# DS1339_RTC_Module.net
KiCad netlist of a schematic drawn in EAGLE
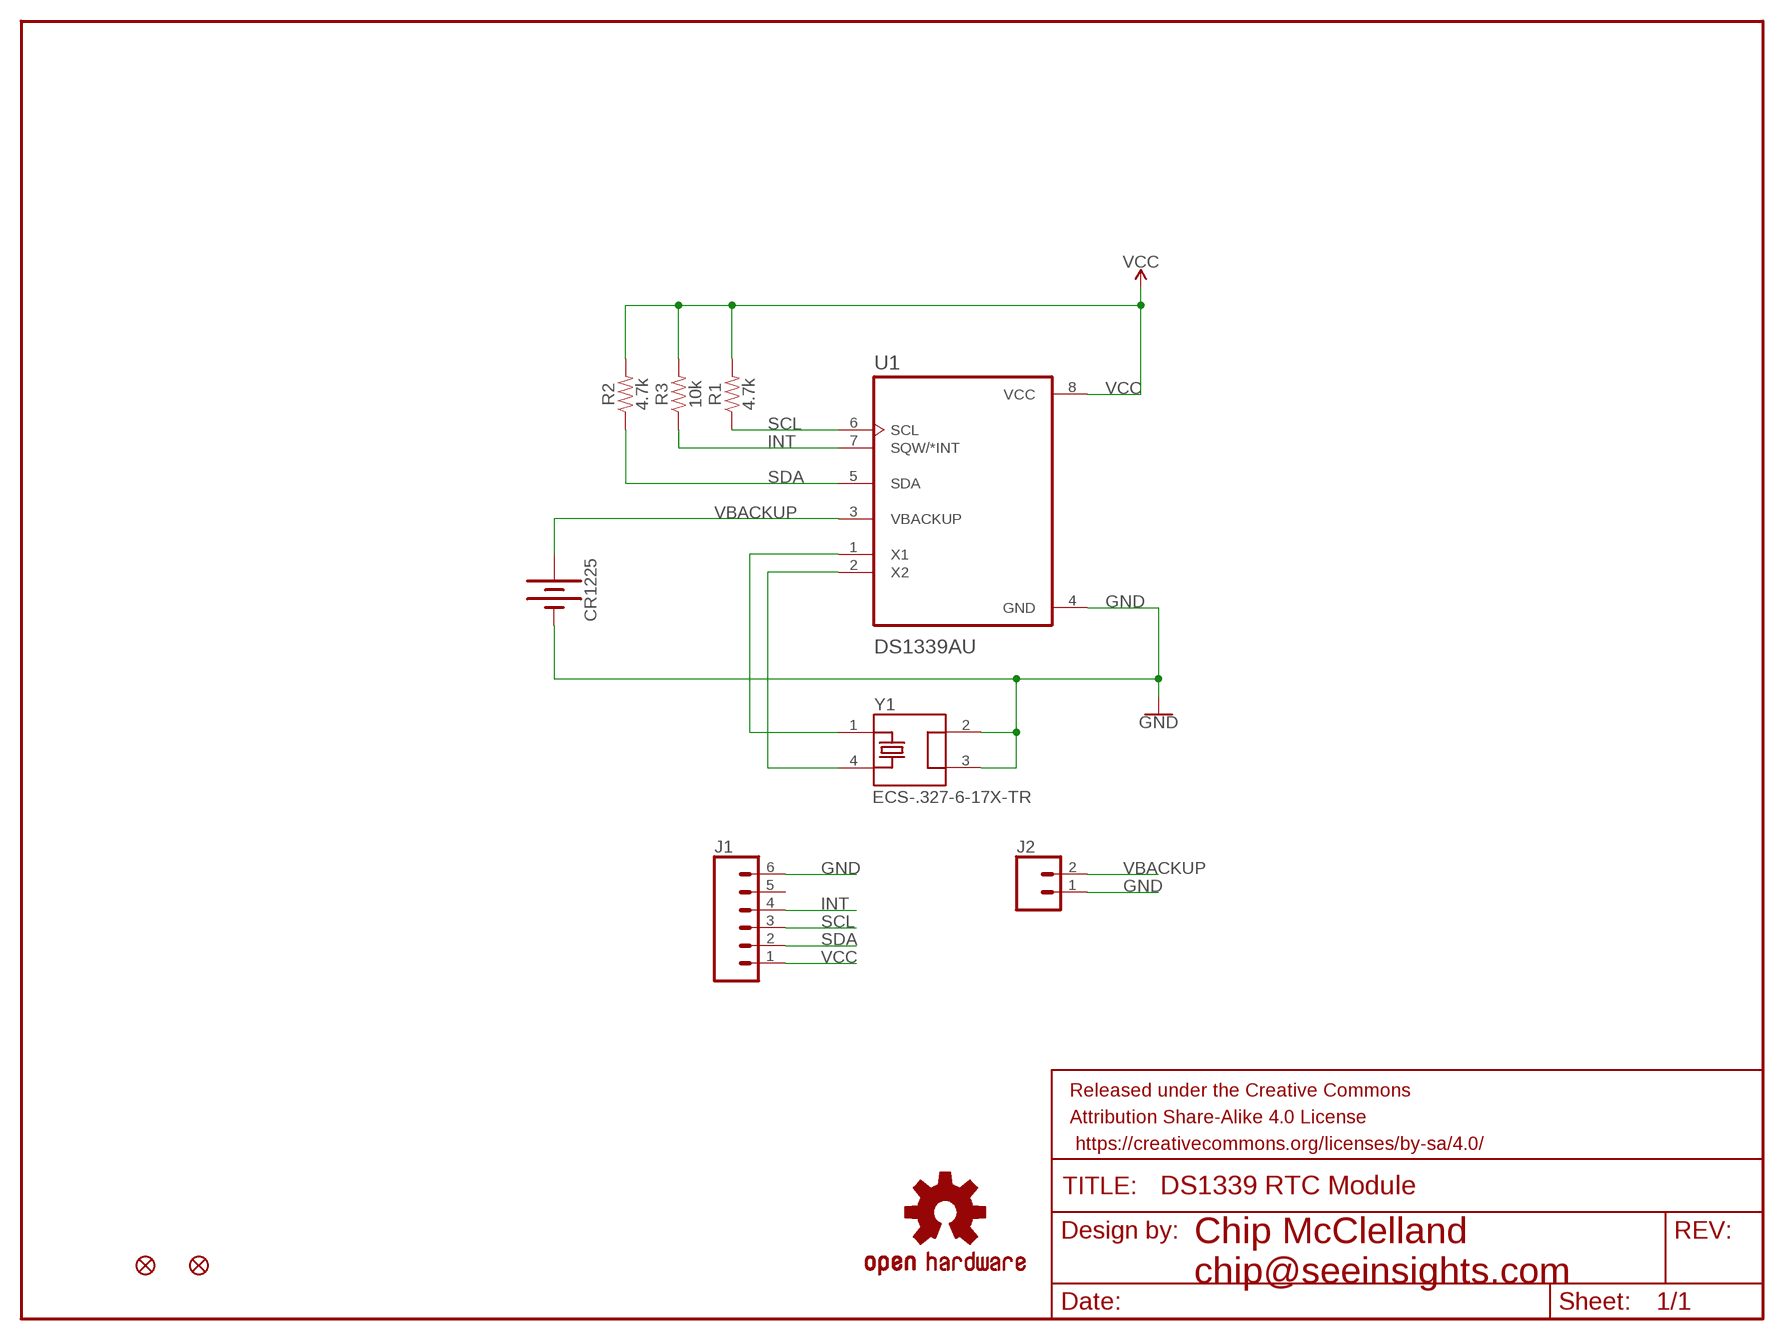
[diagram p0: schematic, sheet 1]

(export (version "E")
  (design (tool "Eeschema 10.0.6"))
  (components
    (comp (ref "CR1225")
      (value "BATTERY-12MM_SMD")
      (footprint "eagle-import:BATTCON_12MM")
      (libsource (lib "eagle-import") (part "BATTERY-12MM_SMD"))
    )
    (comp (ref "FD1")
      (value "FIDUCIALUFIDUCIAL")
      (footprint "eagle-import:FIDUCIAL-MICRO")
      (libsource (lib "eagle-import") (part "FIDUCIALUFIDUCIAL"))
    )
    (comp (ref "FD2")
      (value "FIDUCIALUFIDUCIAL")
      (footprint "eagle-import:FIDUCIAL-MICRO")
      (libsource (lib "eagle-import") (part "FIDUCIALUFIDUCIAL"))
    )
    (comp (ref "FRAME1")
      (value "FRAME-LETTER")
      (footprint "eagle-import:CREATIVE_COMMONS")
      (libsource (lib "eagle-import") (part "FRAME-LETTER"))
    )
    (comp (ref "J1")
      (value "CONN_06LOCK")
      (footprint "eagle-import:1X06_LOCK")
      (libsource (lib "eagle-import") (part "CONN_06LOCK"))
    )
    (comp (ref "J2")
      (value "CONN_02")
      (footprint "eagle-import:1X02")
      (libsource (lib "eagle-import") (part "CONN_02"))
    )
    (comp (ref "LOGO1")
      (value "OSHW-LOGOMINI")
      (footprint "eagle-import:OSHW-LOGO-MINI")
      (libsource (lib "eagle-import") (part "OSHW-LOGOMINI"))
    )
    (comp (ref "R1")
      (value "4.7k")
      (footprint "eagle-import:0805")
      (libsource (lib "eagle-import") (part "RESISTOR0805"))
    )
    (comp (ref "R2")
      (value "4.7k")
      (footprint "eagle-import:0805")
      (libsource (lib "eagle-import") (part "RESISTOR0805"))
    )
    (comp (ref "R3")
      (value "10k")
      (footprint "eagle-import:0805")
      (libsource (lib "eagle-import") (part "RESISTOR0805"))
    )
    (comp (ref "U1")
      (value "DS1339AU")
      (footprint "eagle-import:SOP65P490X110-8N")
      (fields
        (field (name "DIGI-KEY_PART_NUMBER") "DS1339AU+-ND")
        (field (name "MF") "Maxim Integrated")
        (field (name "MP") "DS1339AU+")
      )
      (libsource (lib "eagle-import") (part "DS1339AU"))
    )
    (comp (ref "Y1")
      (value "ECS-.327-6-17X-TR")
      (footprint "eagle-import:XTAL_ECS-.327-6-17X-TR")
      (fields (field (name "DIGI-KEY_PART_NUMBER") "XC1307CT-ND") (field (name "MF") "ECS Inc."))
      (libsource (lib "eagle-import") (part "ECS-.327-6-17X-TR"))
    )
  )
  (nets
    (net (code "1") (name "/INT") (class "Default")
      (node (ref "J1") (pin "4") (pinfunction "4_4") (pintype "passive"))
      (node (ref "R3") (pin "1") (pinfunction "1_1") (pintype "passive"))
      (node (ref "U1") (pin "7") (pinfunction "SQW/*INT_7") (pintype "input"))
    )
    (net (code "2") (name "/SCL") (class "Default")
      (node (ref "J1") (pin "3") (pinfunction "3_3") (pintype "passive"))
      (node (ref "R1") (pin "1") (pinfunction "1_1") (pintype "passive"))
      (node (ref "U1") (pin "6") (pinfunction "SCL_6") (pintype "input"))
    )
    (net (code "3") (name "/SDA") (class "Default")
      (node (ref "J1") (pin "2") (pinfunction "2_2") (pintype "passive"))
      (node (ref "R2") (pin "1") (pinfunction "1_1") (pintype "passive"))
      (node (ref "U1") (pin "5") (pinfunction "SDA_5") (pintype "bidirectional"))
    )
    (net (code "4") (name "/VBACKUP") (class "Default")
      (node (ref "CR1225") (pin "PWR@2") (pinfunction "+_PWR@2") (pintype "power_in"))
      (node (ref "J2") (pin "2") (pinfunction "2_2") (pintype "passive"))
      (node (ref "U1") (pin "3") (pinfunction "VBACKUP_3") (pintype "bidirectional"))
    )
    (net (code "5") (name "GND") (class "Default")
      (node (ref "CR1225") (pin "GND") (pinfunction "-_GND") (pintype "power_in"))
      (node (ref "J1") (pin "6") (pinfunction "6_6") (pintype "passive"))
      (node (ref "J2") (pin "1") (pinfunction "1_1") (pintype "passive"))
      (node (ref "U1") (pin "4") (pinfunction "GND_4") (pintype "power_in"))
      (node (ref "Y1") (pin "2") (pinfunction "2_2") (pintype "passive"))
      (node (ref "Y1") (pin "3") (pinfunction "3_3") (pintype "passive"))
    )
    (net (code "6") (name "Net-(U1-X1)") (class "Default")
      (node (ref "U1") (pin "1") (pinfunction "X1_1") (pintype "bidirectional"))
      (node (ref "Y1") (pin "1") (pinfunction "1_1") (pintype "passive"))
    )
    (net (code "7") (name "Net-(U1-X2)") (class "Default")
      (node (ref "U1") (pin "2") (pinfunction "X2_2") (pintype "bidirectional"))
      (node (ref "Y1") (pin "4") (pinfunction "4_4") (pintype "passive"))
    )
    (net (code "8") (name "VCC") (class "Default")
      (node (ref "J1") (pin "1") (pinfunction "1_1") (pintype "passive"))
      (node (ref "R1") (pin "2") (pinfunction "2_2") (pintype "passive"))
      (node (ref "R2") (pin "2") (pinfunction "2_2") (pintype "passive"))
      (node (ref "R3") (pin "2") (pinfunction "2_2") (pintype "passive"))
      (node (ref "U1") (pin "8") (pinfunction "VCC_8") (pintype "power_in"))
    )
    (net (code "9") (name "unconnected-(J1-Pad5)") (class "Default")
      (node (ref "J1") (pin "5") (pinfunction "5_5") (pintype "passive"))
    )
  )
)
